# 14-pin_SOIC_TSSOP.net
KiCad netlist of a schematic drawn in EAGLE
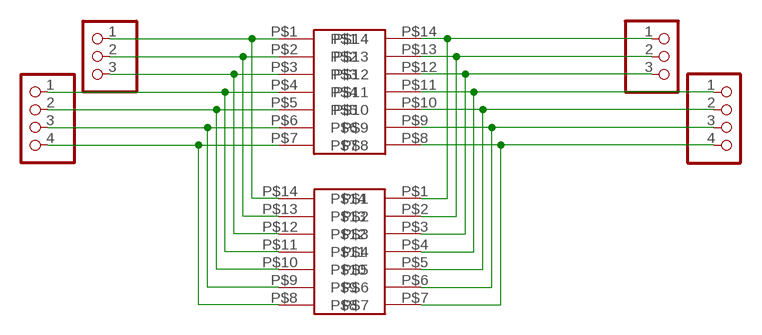
[diagram p0: schematic, sheet 1]

(export (version "E")
  (design (tool "Eeschema 10.0.6"))
  (components
    (comp (ref "JP1")
      (value "PADS-3")
      (footprint "eagle-import:PADS-3")
      (libsource (lib "eagle-import") (part "PADS-3"))
    )
    (comp (ref "JP2")
      (value "PADS-3")
      (footprint "eagle-import:PADS-3")
      (libsource (lib "eagle-import") (part "PADS-3"))
    )
    (comp (ref "JP3")
      (value "PADS-4")
      (footprint "eagle-import:PADS-4")
      (libsource (lib "eagle-import") (part "PADS-4"))
    )
    (comp (ref "JP4")
      (value "PADS-4")
      (footprint "eagle-import:PADS-4")
      (libsource (lib "eagle-import") (part "PADS-4"))
    )
    (comp (ref "U$1")
      (value "14-PINSOIC-NW")
      (footprint "eagle-import:SO14-NW")
      (libsource (lib "eagle-import") (part "14-PINSOIC-NW"))
    )
    (comp (ref "U$2")
      (value "14-PINTSSOP-NW")
      (footprint "eagle-import:TSSOP14-NW")
      (libsource (lib "eagle-import") (part "14-PINTSSOP-NW"))
    )
  )
  (nets
    (net (code "1") (name "Net-(JP1-Pad1)") (class "Default")
      (node (ref "JP1") (pin "1") (pinfunction "1_1") (pintype "passive"))
      (node (ref "U$1") (pin "P$14") (pinfunction "P$14_P$14") (pintype "bidirectional"))
      (node (ref "U$2") (pin "P$1") (pinfunction "P$1_P$1") (pintype "bidirectional"))
    )
    (net (code "2") (name "Net-(JP1-Pad2)") (class "Default")
      (node (ref "JP1") (pin "2") (pinfunction "2_2") (pintype "passive"))
      (node (ref "U$1") (pin "P$13") (pinfunction "P$13_P$13") (pintype "bidirectional"))
      (node (ref "U$2") (pin "P$2") (pinfunction "P$2_P$2") (pintype "bidirectional"))
    )
    (net (code "3") (name "Net-(JP1-Pad3)") (class "Default")
      (node (ref "JP1") (pin "3") (pinfunction "3_3") (pintype "passive"))
      (node (ref "U$1") (pin "P$12") (pinfunction "P$12_P$12") (pintype "bidirectional"))
      (node (ref "U$2") (pin "P$3") (pinfunction "P$3_P$3") (pintype "bidirectional"))
    )
    (net (code "4") (name "Net-(JP2-Pad1)") (class "Default")
      (node (ref "JP2") (pin "1") (pinfunction "1_1") (pintype "passive"))
      (node (ref "U$1") (pin "P$1") (pinfunction "P$1_P$1") (pintype "bidirectional"))
      (node (ref "U$2") (pin "P$14") (pinfunction "P$14_P$14") (pintype "bidirectional"))
    )
    (net (code "5") (name "Net-(JP2-Pad2)") (class "Default")
      (node (ref "JP2") (pin "2") (pinfunction "2_2") (pintype "passive"))
      (node (ref "U$1") (pin "P$2") (pinfunction "P$2_P$2") (pintype "bidirectional"))
      (node (ref "U$2") (pin "P$13") (pinfunction "P$13_P$13") (pintype "bidirectional"))
    )
    (net (code "6") (name "Net-(JP2-Pad3)") (class "Default")
      (node (ref "JP2") (pin "3") (pinfunction "3_3") (pintype "passive"))
      (node (ref "U$1") (pin "P$3") (pinfunction "P$3_P$3") (pintype "bidirectional"))
      (node (ref "U$2") (pin "P$12") (pinfunction "P$12_P$12") (pintype "bidirectional"))
    )
    (net (code "7") (name "Net-(JP3-Pad1)") (class "Default")
      (node (ref "JP3") (pin "1") (pinfunction "1_1") (pintype "passive"))
      (node (ref "U$1") (pin "P$11") (pinfunction "P$11_P$11") (pintype "bidirectional"))
      (node (ref "U$2") (pin "P$4") (pinfunction "P$4_P$4") (pintype "bidirectional"))
    )
    (net (code "8") (name "Net-(JP3-Pad2)") (class "Default")
      (node (ref "JP3") (pin "2") (pinfunction "2_2") (pintype "passive"))
      (node (ref "U$1") (pin "P$10") (pinfunction "P$10_P$10") (pintype "bidirectional"))
      (node (ref "U$2") (pin "P$5") (pinfunction "P$5_P$5") (pintype "bidirectional"))
    )
    (net (code "9") (name "Net-(JP3-Pad3)") (class "Default")
      (node (ref "JP3") (pin "3") (pinfunction "3_3") (pintype "passive"))
      (node (ref "U$1") (pin "P$9") (pinfunction "P$9_P$9") (pintype "bidirectional"))
      (node (ref "U$2") (pin "P$6") (pinfunction "P$6_P$6") (pintype "bidirectional"))
    )
    (net (code "10") (name "Net-(JP3-Pad4)") (class "Default")
      (node (ref "JP3") (pin "4") (pinfunction "4_4") (pintype "passive"))
      (node (ref "U$1") (pin "P$8") (pinfunction "P$8_P$8") (pintype "bidirectional"))
      (node (ref "U$2") (pin "P$7") (pinfunction "P$7_P$7") (pintype "bidirectional"))
    )
    (net (code "11") (name "Net-(JP4-Pad1)") (class "Default")
      (node (ref "JP4") (pin "1") (pinfunction "1_1") (pintype "passive"))
      (node (ref "U$1") (pin "P$4") (pinfunction "P$4_P$4") (pintype "bidirectional"))
      (node (ref "U$2") (pin "P$11") (pinfunction "P$11_P$11") (pintype "bidirectional"))
    )
    (net (code "12") (name "Net-(JP4-Pad2)") (class "Default")
      (node (ref "JP4") (pin "2") (pinfunction "2_2") (pintype "passive"))
      (node (ref "U$1") (pin "P$5") (pinfunction "P$5_P$5") (pintype "bidirectional"))
      (node (ref "U$2") (pin "P$10") (pinfunction "P$10_P$10") (pintype "bidirectional"))
    )
    (net (code "13") (name "Net-(JP4-Pad3)") (class "Default")
      (node (ref "JP4") (pin "3") (pinfunction "3_3") (pintype "passive"))
      (node (ref "U$1") (pin "P$6") (pinfunction "P$6_P$6") (pintype "bidirectional"))
      (node (ref "U$2") (pin "P$9") (pinfunction "P$9_P$9") (pintype "bidirectional"))
    )
    (net (code "14") (name "Net-(JP4-Pad4)") (class "Default")
      (node (ref "JP4") (pin "4") (pinfunction "4_4") (pintype "passive"))
      (node (ref "U$1") (pin "P$7") (pinfunction "P$7_P$7") (pintype "bidirectional"))
      (node (ref "U$2") (pin "P$8") (pinfunction "P$8_P$8") (pintype "bidirectional"))
    )
  )
)
